# Nervo_Board_InMoov.net
KiCad netlist of a schematic drawn in EasyEDA
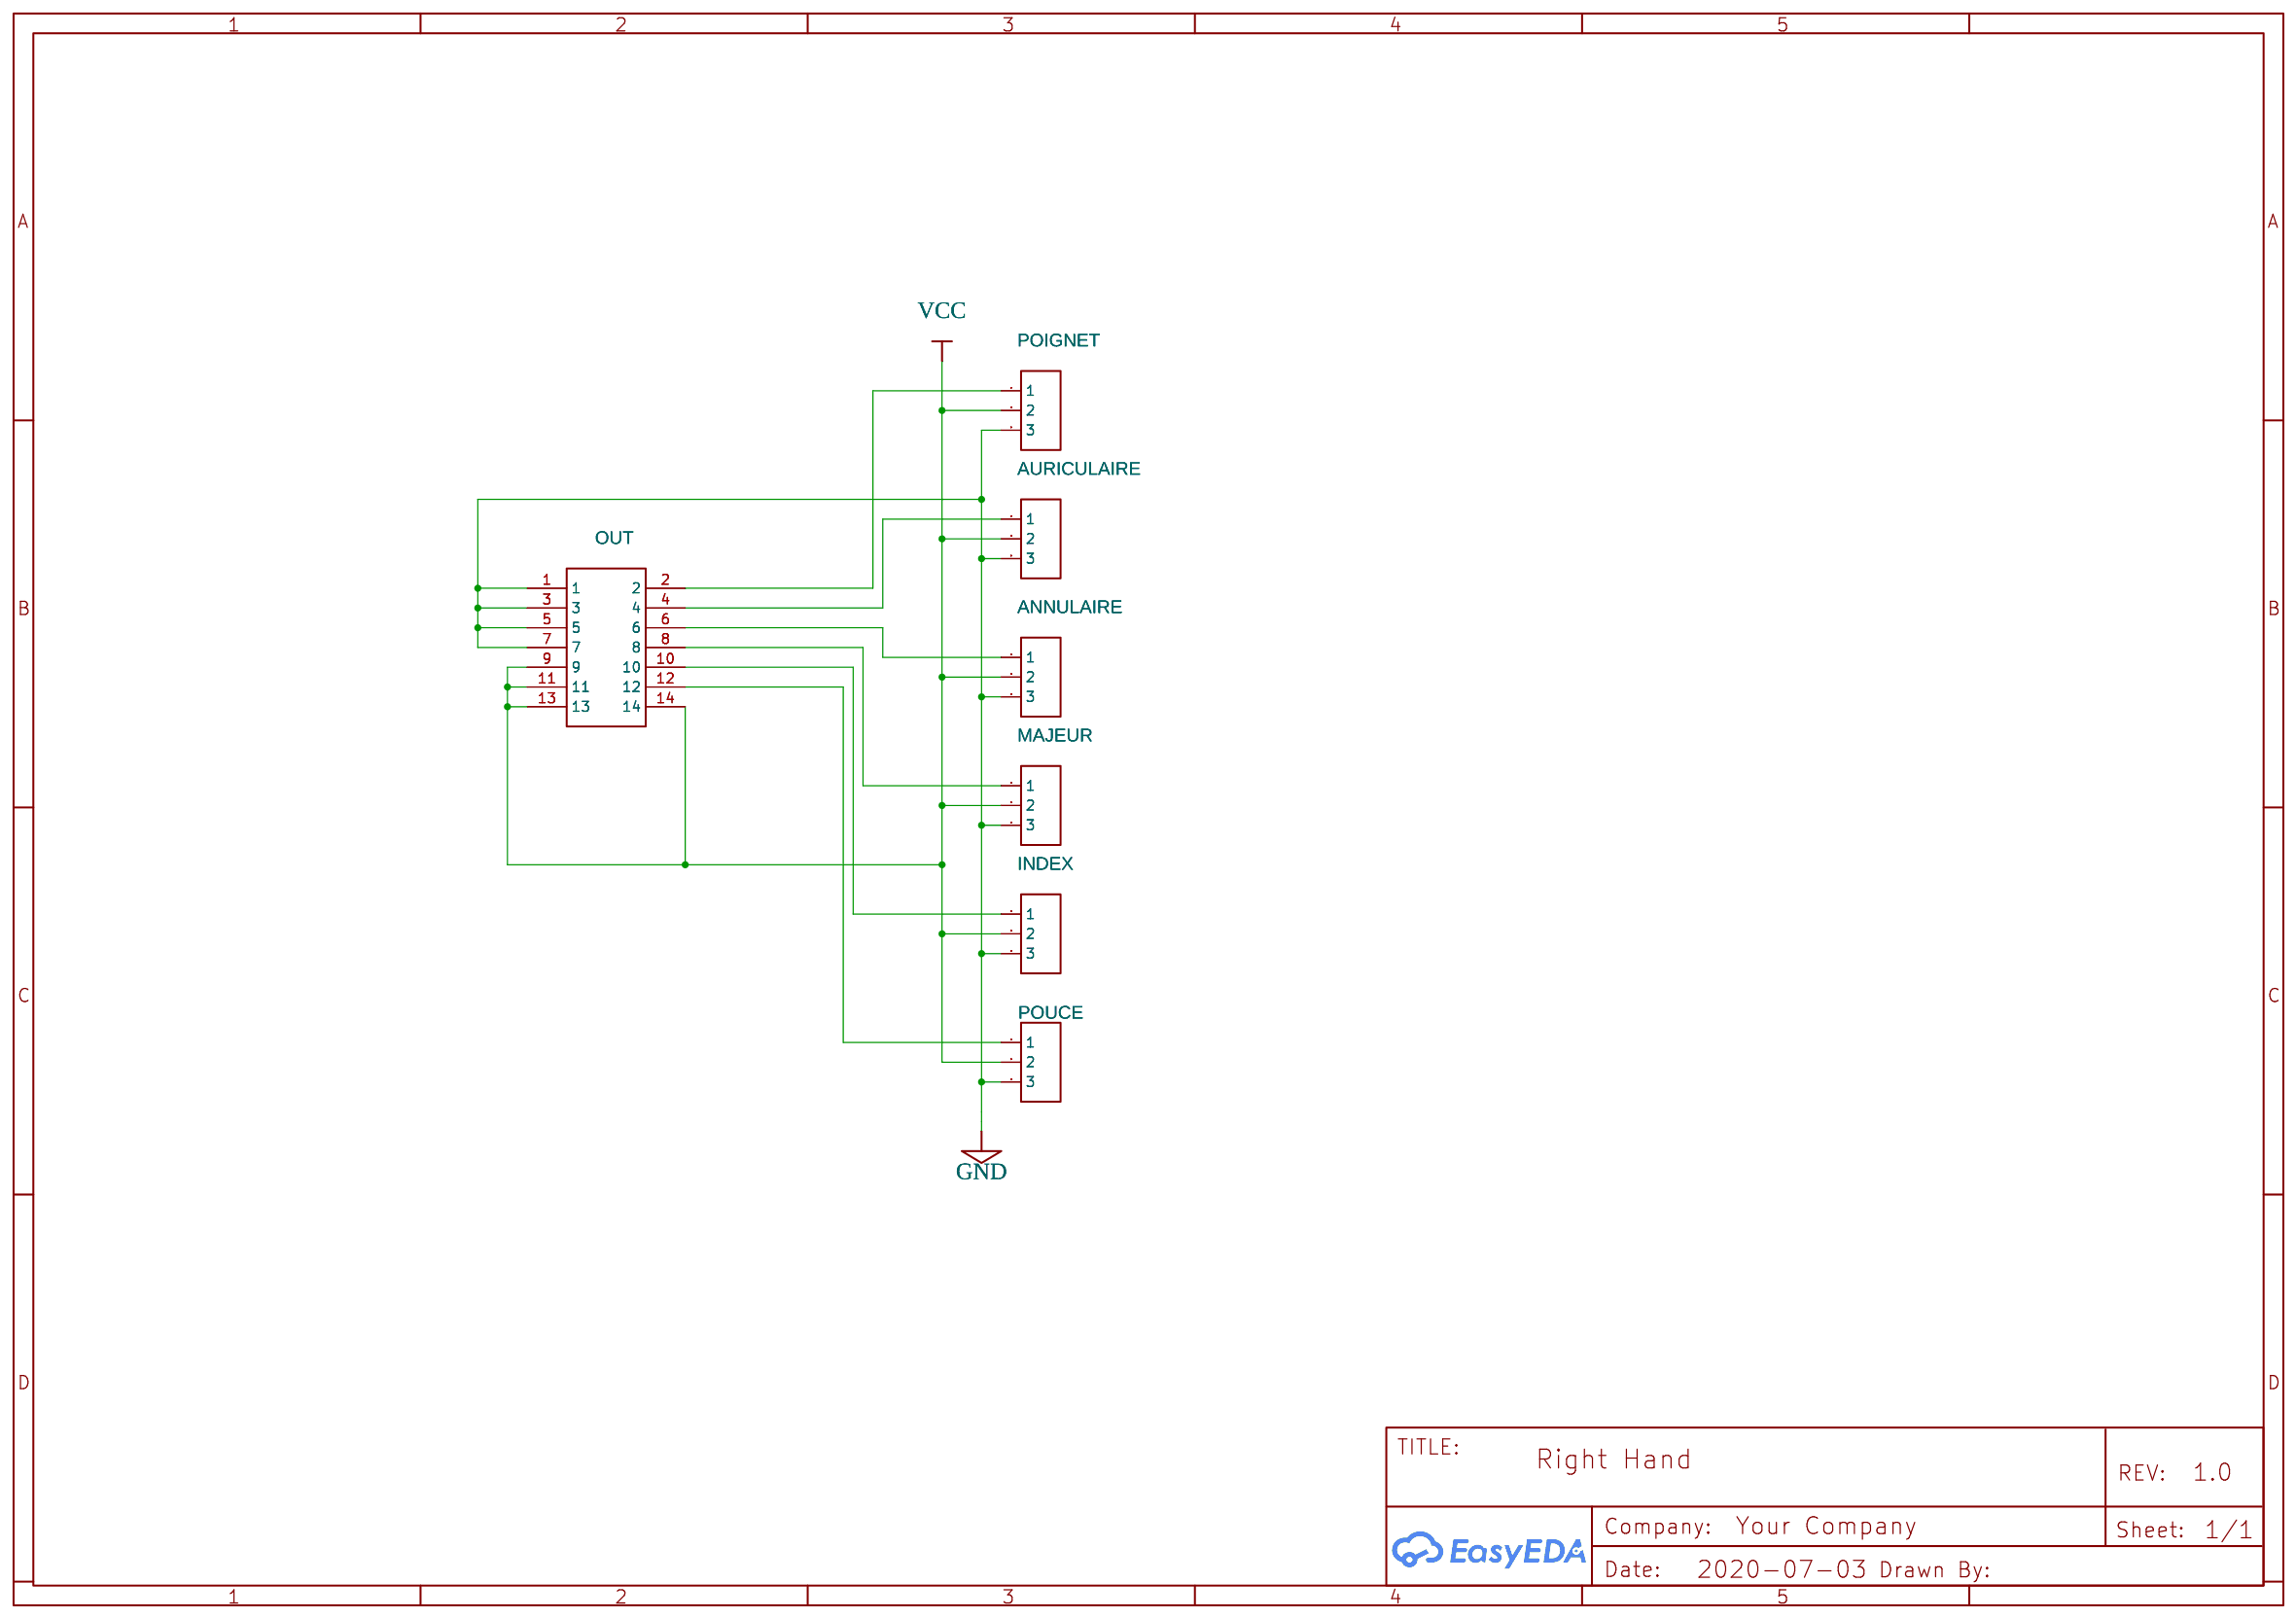
[diagram p0: schematic sheet]

(export (version "E")
  (design (tool "Eeschema 10.0.6"))
  (components
    (comp (ref "ANNULAIRE")
      (value "1")
      (fields
        (field (name "BOM_Manufacturer Part") "Header2.54mm 1*3P")
        (field (name "BOM_Supplier Part") "C49257")
      )
      (libsource (lib "") (part "Header-Male-2.54_1x3_2"))
    )
    (comp (ref "AURICULAIRE")
      (value "1")
      (fields
        (field (name "BOM_Manufacturer Part") "Header2.54mm 1*3P")
        (field (name "BOM_Supplier Part") "C49257")
      )
      (libsource (lib "") (part "Header-Male-2.54_1x3_4"))
    )
    (comp (ref "INDEX")
      (value "1")
      (fields
        (field (name "BOM_Manufacturer Part") "Header2.54mm 1*3P")
        (field (name "BOM_Supplier Part") "C49257")
      )
      (libsource (lib "") (part "Header-Male-2.54_1x3_5"))
    )
    (comp (ref "MAJEUR")
      (value "1")
      (fields
        (field (name "BOM_Manufacturer Part") "Header2.54mm 1*3P")
        (field (name "BOM_Supplier Part") "C49257")
      )
      (libsource (lib "") (part "Header-Male-2.54_1x3_1"))
    )
    (comp (ref "OUT")
      (value "Horn connector/2.0mm2*7P")
      (fields
        (field (name "BOM_Manufacturer Part") "Horn connector/2.0mm2*7P直简牛")
        (field (name "BOM_Supplier Part") "C29428")
      )
      (libsource (lib "") (part "Horn connector/2.0mm2*7P"))
    )
    (comp (ref "POIGNET")
      (value "1")
      (fields
        (field (name "BOM_Manufacturer Part") "Header2.54mm 1*3P")
        (field (name "BOM_Supplier Part") "C49257")
      )
      (libsource (lib "") (part "Header-Male-2.54_1x3_3"))
    )
    (comp (ref "POUCE")
      (value "1")
      (fields
        (field (name "BOM_Manufacturer Part") "Header2.54mm 1*3P")
        (field (name "BOM_Supplier Part") "C49257")
      )
      (libsource (lib "") (part "Header-Male-2.54_1x3"))
    )
  )
  (nets
    (net (code "1") (name "GND") (class "Default")
      (node (ref "ANNULAIRE") (pin "3") (pinfunction "3_3") (pintype "input"))
      (node (ref "AURICULAIRE") (pin "3") (pinfunction "3_3") (pintype "input"))
      (node (ref "INDEX") (pin "3") (pinfunction "3_3") (pintype "input"))
      (node (ref "MAJEUR") (pin "3") (pinfunction "3_3") (pintype "input"))
      (node (ref "OUT") (pin "1") (pinfunction "1_1") (pintype "unspecified"))
      (node (ref "OUT") (pin "3") (pinfunction "3_3") (pintype "unspecified"))
      (node (ref "OUT") (pin "5") (pinfunction "5_5") (pintype "unspecified"))
      (node (ref "OUT") (pin "7") (pinfunction "7_7") (pintype "unspecified"))
      (node (ref "POIGNET") (pin "3") (pinfunction "3_3") (pintype "input"))
      (node (ref "POUCE") (pin "3") (pinfunction "3_3") (pintype "input"))
    )
    (net (code "2") (name "Net-(ANNULAIRE-Pad1)") (class "Default")
      (node (ref "ANNULAIRE") (pin "1") (pinfunction "1_1") (pintype "input"))
      (node (ref "OUT") (pin "6") (pinfunction "6_6") (pintype "unspecified"))
    )
    (net (code "3") (name "Net-(AURICULAIRE-Pad1)") (class "Default")
      (node (ref "AURICULAIRE") (pin "1") (pinfunction "1_1") (pintype "input"))
      (node (ref "OUT") (pin "4") (pinfunction "4_4") (pintype "unspecified"))
    )
    (net (code "4") (name "Net-(INDEX-Pad1)") (class "Default")
      (node (ref "INDEX") (pin "1") (pinfunction "1_1") (pintype "input"))
      (node (ref "OUT") (pin "10") (pinfunction "10_10") (pintype "unspecified"))
    )
    (net (code "5") (name "Net-(MAJEUR-Pad1)") (class "Default")
      (node (ref "MAJEUR") (pin "1") (pinfunction "1_1") (pintype "input"))
      (node (ref "OUT") (pin "8") (pinfunction "8_8") (pintype "unspecified"))
    )
    (net (code "6") (name "Net-(OUT-Pad2)") (class "Default")
      (node (ref "OUT") (pin "2") (pinfunction "2_2") (pintype "unspecified"))
      (node (ref "POIGNET") (pin "1") (pinfunction "1_1") (pintype "input"))
    )
    (net (code "7") (name "Net-(OUT-Pad12)") (class "Default")
      (node (ref "OUT") (pin "12") (pinfunction "12_12") (pintype "unspecified"))
      (node (ref "POUCE") (pin "1") (pinfunction "1_1") (pintype "input"))
    )
    (net (code "8") (name "VCC") (class "Default")
      (node (ref "ANNULAIRE") (pin "2") (pinfunction "2_2") (pintype "input"))
      (node (ref "AURICULAIRE") (pin "2") (pinfunction "2_2") (pintype "input"))
      (node (ref "INDEX") (pin "2") (pinfunction "2_2") (pintype "input"))
      (node (ref "MAJEUR") (pin "2") (pinfunction "2_2") (pintype "input"))
      (node (ref "OUT") (pin "11") (pinfunction "11_11") (pintype "unspecified"))
      (node (ref "OUT") (pin "13") (pinfunction "13_13") (pintype "unspecified"))
      (node (ref "OUT") (pin "14") (pinfunction "14_14") (pintype "unspecified"))
      (node (ref "OUT") (pin "9") (pinfunction "9_9") (pintype "unspecified"))
      (node (ref "POIGNET") (pin "2") (pinfunction "2_2") (pintype "input"))
      (node (ref "POUCE") (pin "2") (pinfunction "2_2") (pintype "input"))
    )
  )
)
